# Sheet4.net
KiCad netlist of a schematic drawn in Altium Designer
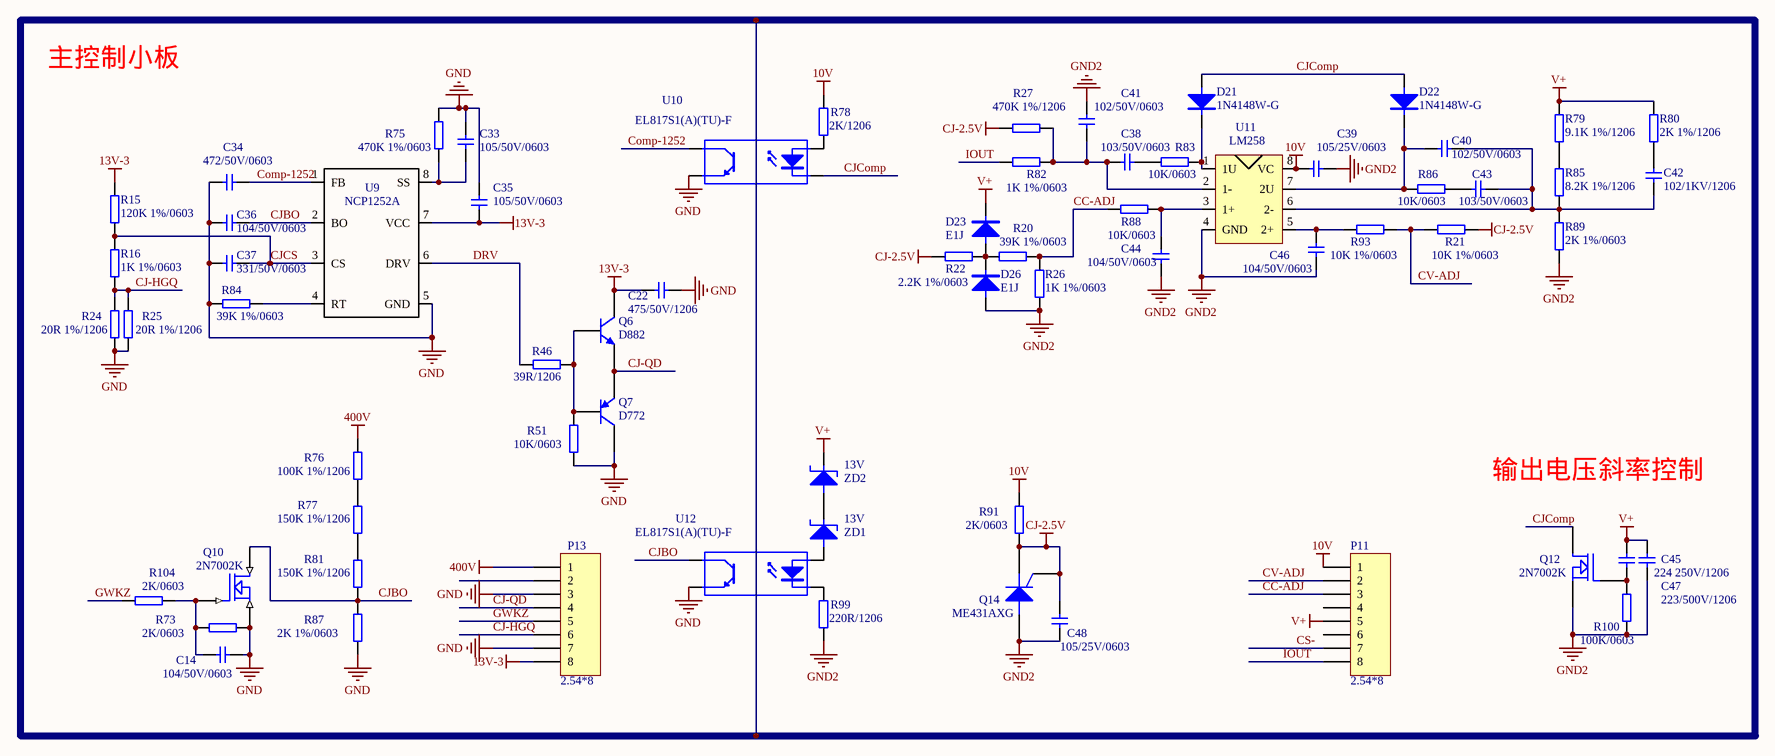
[diagram p0: Sheet4.SchDoc]

(export (version "E")
  (design (tool "Eeschema 10.0.6"))
  (components
    (comp (ref "C14")
      (value "104/50V/0603")
      (footprint "0603")
      (description "Capacitor")
      (libsource (lib "*") (part "CAP"))
    )
    (comp (ref "C22")
      (value "475/50V/1206")
      (footprint "1206")
      (description "Capacitor")
      (libsource (lib "*") (part "CAP"))
    )
    (comp (ref "C33")
      (value "105/50V/0603")
      (footprint "0603")
      (description "Capacitor")
      (libsource (lib "*") (part "CAP"))
    )
    (comp (ref "C34")
      (value "472/50V/0603")
      (footprint "0603")
      (description "Capacitor")
      (libsource (lib "*") (part "CAP"))
    )
    (comp (ref "C35")
      (value "105/50V/0603")
      (footprint "0603")
      (description "Capacitor")
      (libsource (lib "*") (part "CAP"))
    )
    (comp (ref "C36")
      (value "104/50V/0603")
      (footprint "0603")
      (description "Capacitor")
      (libsource (lib "*") (part "CAP"))
    )
    (comp (ref "C37")
      (value "331/50V/0603")
      (footprint "0603")
      (description "Capacitor")
      (libsource (lib "*") (part "CAP"))
    )
    (comp (ref "C38")
      (value "103/50V/0603")
      (footprint "0603")
      (description "Capacitor")
      (libsource (lib "*") (part "CAP"))
    )
    (comp (ref "C39")
      (value "105/25V/0603")
      (footprint "0603")
      (description "Capacitor")
      (libsource (lib "*") (part "CAP"))
    )
    (comp (ref "C40")
      (value "102/50V/0603")
      (footprint "0603")
      (description "Capacitor")
      (libsource (lib "*") (part "CAP"))
    )
    (comp (ref "C41")
      (value "102/50V/0603")
      (footprint "0603")
      (description "Capacitor")
      (libsource (lib "*") (part "CAP"))
    )
    (comp (ref "C42")
      (value "102/1KV/1206")
      (footprint "1206")
      (description "Capacitor")
      (libsource (lib "") (part "CAP_1"))
    )
    (comp (ref "C43")
      (value "103/50V/0603")
      (footprint "0603")
      (description "Capacitor")
      (libsource (lib "*") (part "CAP"))
    )
    (comp (ref "C44")
      (value "104/50V/0603")
      (footprint "0603")
      (description "Capacitor")
      (libsource (lib "*") (part "CAP"))
    )
    (comp (ref "C45")
      (value "224 250V/1206")
      (footprint "1206")
      (description "Capacitor")
      (libsource (lib "*") (part "CAP"))
    )
    (comp (ref "C46")
      (value "104/50V/0603")
      (footprint "0603")
      (description "Capacitor")
      (libsource (lib "*") (part "CAP"))
    )
    (comp (ref "C47")
      (value "223/500V/1206")
      (footprint "1206")
      (description "Capacitor")
      (libsource (lib "*") (part "CAP"))
    )
    (comp (ref "C48")
      (value "105/25V/0603")
      (footprint "0603")
      (description "Capacitor")
      (libsource (lib "*") (part "CAP"))
    )
    (comp (ref "D21")
      (value "1N4148W-G")
      (footprint "SOD-123")
      (description "Diode")
      (libsource (lib "sch123") (part "DIODE"))
    )
    (comp (ref "D22")
      (value "1N4148W-G")
      (footprint "SOD-123")
      (description "Diode")
      (libsource (lib "sch123") (part "DIODE"))
    )
    (comp (ref "D23")
      (value "E1J")
      (footprint "SOD-123")
      (description "Diode")
      (libsource (lib "sch123") (part "DIODE"))
    )
    (comp (ref "D26")
      (value "E1J")
      (footprint "SOD-123")
      (description "Diode")
      (libsource (lib "sch123") (part "DIODE"))
    )
    (comp (ref "P11")
      (value "2.54*8")
      (footprint "2.54*8")
      (description "Header, 8-Pin")
      (fields (field (name "PUBLISHER") "Altium Limited"))
      (libsource (lib "Miscellaneous Connectors") (part "Header 8"))
    )
    (comp (ref "P13")
      (value "2.54*8")
      (footprint "2.54*8")
      (description "Header, 8-Pin")
      (fields (field (name "PUBLISHER") "Altium Limited"))
      (libsource (lib "Miscellaneous Connectors") (part "Header 8"))
    )
    (comp (ref "Q6")
      (value "D882")
      (footprint "D882")
      (description "NPN General Purpose Amplifier")
      (fields (field (name "PUBLISHER") "Altium Limited"))
      (libsource (lib "Miscellaneous Devices") (part "2N3904"))
    )
    (comp (ref "Q7")
      (value "D772")
      (footprint "D772")
      (description "PNP General Purpose Amplifier")
      (fields (field (name "PUBLISHER") "Altium Limited"))
      (libsource (lib "Miscellaneous Devices") (part "2N3906"))
    )
    (comp (ref "Q10") (value "2N7002K") (footprint "SOT-23/MOS") (libsource (lib "sch123") (part "MOSFET N")))
    (comp (ref "Q12") (value "2N7002K") (footprint "SOT-23/MOS") (libsource (lib "sch123") (part "MOSFET N")))
    (comp (ref "Q14")
      (value "ME431AXG")
      (footprint "ME431AXG")
      (description "Silicon Controlled Rectifier")
      (fields (field (name "PUBLISHER") "Altium Limited"))
      (libsource (lib "Miscellaneous Devices") (part "SCR"))
    )
    (comp (ref "R15") (value "120K 1%/0603") (footprint "0603") (libsource (lib "*") (part "RES2")))
    (comp (ref "R16") (value "1K 1%/0603") (footprint "0603") (libsource (lib "*") (part "RES2")))
    (comp (ref "R20") (value "39K 1%/0603") (footprint "0603") (libsource (lib "sch123") (part "RES2")))
    (comp (ref "R21") (value "10K 1%/0603") (footprint "0603") (libsource (lib "sch123") (part "RES2")))
    (comp (ref "R22") (value "2.2K 1%/0603") (footprint "0603") (libsource (lib "sch123") (part "RES2")))
    (comp (ref "R24") (value "20R 1%/1206") (footprint "1206") (libsource (lib "*") (part "RES2")))
    (comp (ref "R25") (value "20R 1%/1206") (footprint "1206") (libsource (lib "*") (part "RES2")))
    (comp (ref "R26") (value "1K 1%/0603") (footprint "0603") (libsource (lib "sch123") (part "RES2")))
    (comp (ref "R27") (value "470K 1%/1206") (footprint "1206") (libsource (lib "sch123") (part "RES2")))
    (comp (ref "R46") (value "39R/1206") (footprint "1206") (libsource (lib "") (part "RES2_1")))
    (comp (ref "R51") (value "10K/0603") (footprint "0603") (libsource (lib "*") (part "RES2")))
    (comp (ref "R73") (value "2K/0603") (footprint "0603") (libsource (lib "sch123") (part "RES2")))
    (comp (ref "R75") (value "470K 1%/0603") (footprint "0603") (libsource (lib "sch123") (part "RES2")))
    (comp (ref "R76") (value "100K 1%/1206") (footprint "1206") (libsource (lib "*") (part "RES2")))
    (comp (ref "R77") (value "150K 1%/1206") (footprint "1206") (libsource (lib "*") (part "RES2")))
    (comp (ref "R78") (value "2K/1206") (footprint "1206") (libsource (lib "*") (part "RES2")))
    (comp (ref "R79") (value "9.1K 1%/1206") (footprint "1206") (libsource (lib "sch123") (part "RES2")))
    (comp (ref "R80") (value "2K 1%/1206") (footprint "1206") (libsource (lib "sch123") (part "RES2")))
    (comp (ref "R81") (value "150K 1%/1206") (footprint "1206") (libsource (lib "*") (part "RES2")))
    (comp (ref "R82") (value "1K 1%/0603") (footprint "0603") (libsource (lib "sch123") (part "RES2")))
    (comp (ref "R83") (value "10K/0603") (footprint "0603") (libsource (lib "sch123") (part "RES2")))
    (comp (ref "R84") (value "39K 1%/0603") (footprint "0603") (libsource (lib "sch123") (part "RES2")))
    (comp (ref "R85") (value "8.2K 1%/1206") (footprint "1206") (libsource (lib "sch123") (part "RES2")))
    (comp (ref "R86") (value "10K/0603") (footprint "0603") (libsource (lib "sch123") (part "RES2")))
    (comp (ref "R87") (value "2K 1%/0603") (footprint "0603") (libsource (lib "sch123") (part "RES2")))
    (comp (ref "R88") (value "10K/0603") (footprint "0603") (libsource (lib "sch123") (part "RES2")))
    (comp (ref "R89") (value "2K 1%/0603") (footprint "0603") (libsource (lib "sch123") (part "RES2")))
    (comp (ref "R91") (value "2K/0603") (footprint "0603") (libsource (lib "sch123") (part "RES2")))
    (comp (ref "R93") (value "10K 1%/0603") (footprint "0603") (libsource (lib "sch123") (part "RES2")))
    (comp (ref "R99") (value "220R/1206") (footprint "1206") (libsource (lib "*") (part "RES2")))
    (comp (ref "R100") (value "100K/0603") (footprint "0603") (libsource (lib "sch123") (part "RES2")))
    (comp (ref "R104") (value "2K/0603") (footprint "0603") (libsource (lib "sch123") (part "RES2")))
    (comp (ref "U9") (value "NCP1252A") (footprint "SOP8") (libsource (lib "Schlib1") (part "Component_1")))
    (comp (ref "U10")
      (value "EL817S1(A)(TU)-F")
      (footprint "EL817A")
      (description "4-Pin Phototransistor Optocoupler")
      (fields (field (name "PUBLISHER") "Altium Limited"))
      (libsource (lib "Miscellaneous Devices") (part "Optoisolator1"))
    )
    (comp (ref "U11") (value "LM258") (footprint "SOp8") (libsource (lib "Schlib1") (part "AP4310")))
    (comp (ref "U12")
      (value "EL817S1(A)(TU)-F")
      (footprint "EL817A")
      (description "4-Pin Phototransistor Optocoupler")
      (fields (field (name "PUBLISHER") "Altium Limited"))
      (libsource (lib "Miscellaneous Devices") (part "Optoisolator1"))
    )
    (comp (ref "ZD1")
      (value "13V")
      (footprint "SOD-123")
      (description "Diode Tunnel")
      (libsource (lib "sch123") (part "DIODE TUNNEL"))
    )
    (comp (ref "ZD2")
      (value "13V")
      (footprint "SOD-123")
      (description "Diode Tunnel")
      (libsource (lib "sch123") (part "DIODE TUNNEL"))
    )
  )
  (nets
    (net (code "1") (name "/CC-ADJ") (class "Default")
      (node (ref "P11") (pin "3") (pinfunction "3_3") (pintype "passive"))
      (node (ref "R20") (pin "2") (pinfunction "2_2") (pintype "passive"))
      (node (ref "R26") (pin "2") (pinfunction "2_2") (pintype "passive"))
      (node (ref "R88") (pin "1") (pinfunction "1_1") (pintype "passive"))
    )
    (net (code "2") (name "/CJ-HGQ") (class "Default")
      (node (ref "P13") (pin "6") (pinfunction "6_6") (pintype "passive"))
      (node (ref "R16") (pin "2") (pinfunction "2_2") (pintype "passive"))
      (node (ref "R24") (pin "1") (pinfunction "1_1") (pintype "passive"))
      (node (ref "R25") (pin "1") (pinfunction "1_1") (pintype "passive"))
    )
    (net (code "3") (name "/CJ-QD") (class "Default")
      (node (ref "P13") (pin "4") (pinfunction "4_4") (pintype "passive"))
      (node (ref "Q6") (pin "1") (pinfunction "E_1") (pintype "passive"))
      (node (ref "Q7") (pin "1") (pinfunction "E_1") (pintype "passive"))
    )
    (net (code "4") (name "/CJBO") (class "Default")
      (node (ref "C36") (pin "1") (pinfunction "1_1") (pintype "passive"))
      (node (ref "Q10") (pin "D") (pinfunction "D_D") (pintype "input"))
      (node (ref "R81") (pin "1") (pinfunction "1_1") (pintype "passive"))
      (node (ref "R87") (pin "1") (pinfunction "1_1") (pintype "passive"))
      (node (ref "U12") (pin "4") (pinfunction "C_4") (pintype "passive"))
      (node (ref "U9") (pin "2") (pinfunction "BO_2") (pintype "passive"))
    )
    (net (code "5") (name "/CJCS") (class "Default")
      (node (ref "C37") (pin "1") (pinfunction "1_1") (pintype "passive"))
      (node (ref "R15") (pin "2") (pinfunction "2_2") (pintype "passive"))
      (node (ref "R16") (pin "1") (pinfunction "1_1") (pintype "passive"))
      (node (ref "U9") (pin "3") (pinfunction "CS_3") (pintype "passive"))
    )
    (net (code "6") (name "/CJComp") (class "Default")
      (node (ref "D21") (pin "1") (pinfunction "A_1") (pintype "passive"))
      (node (ref "D22") (pin "1") (pinfunction "A_1") (pintype "passive"))
      (node (ref "Q12") (pin "D") (pinfunction "D_D") (pintype "input"))
      (node (ref "U10") (pin "2") (pinfunction "K_2") (pintype "passive"))
    )
    (net (code "7") (name "/CS-") (class "Default")
      (node (ref "P11") (pin "7") (pinfunction "7_7") (pintype "passive"))
    )
    (net (code "8") (name "/CV-ADJ") (class "Default")
      (node (ref "P11") (pin "2") (pinfunction "2_2") (pintype "passive"))
      (node (ref "R21") (pin "1") (pinfunction "1_1") (pintype "passive"))
      (node (ref "R93") (pin "2") (pinfunction "2_2") (pintype "passive"))
    )
    (net (code "9") (name "/Comp-1252") (class "Default")
      (node (ref "C34") (pin "1") (pinfunction "1_1") (pintype "passive"))
      (node (ref "U10") (pin "4") (pinfunction "C_4") (pintype "passive"))
      (node (ref "U9") (pin "1") (pinfunction "FB_1") (pintype "passive"))
    )
    (net (code "10") (name "/DRV") (class "Default")
      (node (ref "R46") (pin "2") (pinfunction "2_2") (pintype "passive"))
      (node (ref "U9") (pin "6") (pinfunction "DRV_6") (pintype "passive"))
    )
    (net (code "11") (name "/GWKZ") (class "Default")
      (node (ref "P13") (pin "5") (pinfunction "5_5") (pintype "passive"))
      (node (ref "R104") (pin "2") (pinfunction "2_2") (pintype "passive"))
    )
    (net (code "12") (name "/IOUT") (class "Default")
      (node (ref "P11") (pin "8") (pinfunction "8_8") (pintype "passive"))
      (node (ref "R82") (pin "2") (pinfunction "2_2") (pintype "passive"))
    )
    (net (code "13") (name "10V") (class "Default")
      (node (ref "C39") (pin "2") (pinfunction "2_2") (pintype "passive"))
      (node (ref "P11") (pin "1") (pinfunction "1_1") (pintype "passive"))
      (node (ref "R78") (pin "2") (pinfunction "2_2") (pintype "passive"))
      (node (ref "R91") (pin "2") (pinfunction "2_2") (pintype "passive"))
      (node (ref "U11") (pin "8") (pinfunction "VC_8") (pintype "passive"))
    )
    (net (code "14") (name "13V-3") (class "Default")
      (node (ref "C22") (pin "2") (pinfunction "2_2") (pintype "passive"))
      (node (ref "C35") (pin "1") (pinfunction "1_1") (pintype "passive"))
      (node (ref "P13") (pin "8") (pinfunction "8_8") (pintype "passive"))
      (node (ref "Q6") (pin "3") (pinfunction "C_3") (pintype "passive"))
      (node (ref "R15") (pin "1") (pinfunction "1_1") (pintype "passive"))
      (node (ref "U9") (pin "7") (pinfunction "VCC_7") (pintype "passive"))
    )
    (net (code "15") (name "400V") (class "Default")
      (node (ref "P13") (pin "1") (pinfunction "1_1") (pintype "passive"))
      (node (ref "R76") (pin "2") (pinfunction "2_2") (pintype "passive"))
    )
    (net (code "16") (name "CJ-2.5V") (class "Default")
      (node (ref "C48") (pin "2") (pinfunction "2_2") (pintype "passive"))
      (node (ref "Q14") (pin "2") (pinfunction "G_2") (pintype "passive"))
      (node (ref "Q14") (pin "3") (pinfunction "K_3") (pintype "passive"))
      (node (ref "R21") (pin "2") (pinfunction "2_2") (pintype "passive"))
      (node (ref "R22") (pin "1") (pinfunction "1_1") (pintype "passive"))
      (node (ref "R27") (pin "2") (pinfunction "2_2") (pintype "passive"))
      (node (ref "R91") (pin "1") (pinfunction "1_1") (pintype "passive"))
    )
    (net (code "17") (name "GND") (class "Default")
      (node (ref "C14") (pin "1") (pinfunction "1_1") (pintype "passive"))
      (node (ref "C22") (pin "1") (pinfunction "1_1") (pintype "passive"))
      (node (ref "C33") (pin "2") (pinfunction "2_2") (pintype "passive"))
      (node (ref "C34") (pin "2") (pinfunction "2_2") (pintype "passive"))
      (node (ref "C35") (pin "2") (pinfunction "2_2") (pintype "passive"))
      (node (ref "C36") (pin "2") (pinfunction "2_2") (pintype "passive"))
      (node (ref "C37") (pin "2") (pinfunction "2_2") (pintype "passive"))
      (node (ref "P13") (pin "3") (pinfunction "3_3") (pintype "passive"))
      (node (ref "P13") (pin "7") (pinfunction "7_7") (pintype "passive"))
      (node (ref "Q10") (pin "S") (pinfunction "S_S") (pintype "input"))
      (node (ref "Q7") (pin "3") (pinfunction "C_3") (pintype "passive"))
      (node (ref "R24") (pin "2") (pinfunction "2_2") (pintype "passive"))
      (node (ref "R25") (pin "2") (pinfunction "2_2") (pintype "passive"))
      (node (ref "R51") (pin "1") (pinfunction "1_1") (pintype "passive"))
      (node (ref "R73") (pin "1") (pinfunction "1_1") (pintype "passive"))
      (node (ref "R75") (pin "2") (pinfunction "2_2") (pintype "passive"))
      (node (ref "R84") (pin "1") (pinfunction "1_1") (pintype "passive"))
      (node (ref "R87") (pin "2") (pinfunction "2_2") (pintype "passive"))
      (node (ref "U10") (pin "3") (pinfunction "E_3") (pintype "passive"))
      (node (ref "U12") (pin "3") (pinfunction "E_3") (pintype "passive"))
      (node (ref "U9") (pin "5") (pinfunction "GND_5") (pintype "passive"))
    )
    (net (code "18") (name "GND2") (class "Default")
      (node (ref "C39") (pin "1") (pinfunction "1_1") (pintype "passive"))
      (node (ref "C41") (pin "2") (pinfunction "2_2") (pintype "passive"))
      (node (ref "C44") (pin "1") (pinfunction "1_1") (pintype "passive"))
      (node (ref "C45") (pin "2") (pinfunction "2_2") (pintype "passive"))
      (node (ref "C46") (pin "2") (pinfunction "2_2") (pintype "passive"))
      (node (ref "C48") (pin "1") (pinfunction "1_1") (pintype "passive"))
      (node (ref "D26") (pin "1") (pinfunction "A_1") (pintype "passive"))
      (node (ref "Q12") (pin "S") (pinfunction "S_S") (pintype "input"))
      (node (ref "Q14") (pin "1") (pinfunction "A_1") (pintype "passive"))
      (node (ref "R100") (pin "1") (pinfunction "1_1") (pintype "passive"))
      (node (ref "R26") (pin "1") (pinfunction "1_1") (pintype "passive"))
      (node (ref "R89") (pin "1") (pinfunction "1_1") (pintype "passive"))
      (node (ref "R99") (pin "1") (pinfunction "1_1") (pintype "passive"))
      (node (ref "U11") (pin "4") (pinfunction "GND_4") (pintype "passive"))
    )
    (net (code "19") (name "Net-(C14-Pad2)") (class "Default")
      (node (ref "C14") (pin "2") (pinfunction "2_2") (pintype "passive"))
      (node (ref "Q10") (pin "G") (pinfunction "G_G") (pintype "input"))
      (node (ref "R104") (pin "1") (pinfunction "1_1") (pintype "passive"))
      (node (ref "R73") (pin "2") (pinfunction "2_2") (pintype "passive"))
    )
    (net (code "20") (name "Net-(C38-Pad1)") (class "Default")
      (node (ref "C38") (pin "1") (pinfunction "1_1") (pintype "passive"))
      (node (ref "R83") (pin "1") (pinfunction "1_1") (pintype "passive"))
    )
    (net (code "21") (name "Net-(C42-Pad2)") (class "Default")
      (node (ref "C42") (pin "2") (pinfunction "2_2") (pintype "passive"))
      (node (ref "R80") (pin "1") (pinfunction "1_1") (pintype "passive"))
    )
    (net (code "22") (name "Net-(C43-Pad2)") (class "Default")
      (node (ref "C43") (pin "2") (pinfunction "2_2") (pintype "passive"))
      (node (ref "R86") (pin "2") (pinfunction "2_2") (pintype "passive"))
    )
    (net (code "23") (name "Net-(C47-Pad2)") (class "Default")
      (node (ref "C47") (pin "2") (pinfunction "2_2") (pintype "passive"))
      (node (ref "Q12") (pin "G") (pinfunction "G_G") (pintype "input"))
      (node (ref "R100") (pin "2") (pinfunction "2_2") (pintype "passive"))
    )
    (net (code "24") (name "Net-(D21-K)") (class "Default")
      (node (ref "D21") (pin "2") (pinfunction "K_2") (pintype "passive"))
      (node (ref "R83") (pin "2") (pinfunction "2_2") (pintype "passive"))
      (node (ref "U11") (pin "1") (pinfunction "1U_1") (pintype "passive"))
    )
    (net (code "25") (name "Net-(D22-K)") (class "Default")
      (node (ref "C40") (pin "2") (pinfunction "2_2") (pintype "passive"))
      (node (ref "D22") (pin "2") (pinfunction "K_2") (pintype "passive"))
      (node (ref "R86") (pin "1") (pinfunction "1_1") (pintype "passive"))
      (node (ref "U11") (pin "7") (pinfunction "2U_7") (pintype "passive"))
    )
    (net (code "26") (name "Net-(D23-A)") (class "Default")
      (node (ref "D23") (pin "1") (pinfunction "A_1") (pintype "passive"))
      (node (ref "D26") (pin "2") (pinfunction "K_2") (pintype "passive"))
      (node (ref "R20") (pin "1") (pinfunction "1_1") (pintype "passive"))
      (node (ref "R22") (pin "2") (pinfunction "2_2") (pintype "passive"))
    )
    (net (code "27") (name "Net-(Q6-B)") (class "Default")
      (node (ref "Q6") (pin "2") (pinfunction "B_2") (pintype "passive"))
      (node (ref "Q7") (pin "2") (pinfunction "B_2") (pintype "passive"))
      (node (ref "R46") (pin "1") (pinfunction "1_1") (pintype "passive"))
      (node (ref "R51") (pin "2") (pinfunction "2_2") (pintype "passive"))
    )
    (net (code "28") (name "Net-(R76-Pad1)") (class "Default")
      (node (ref "R76") (pin "1") (pinfunction "1_1") (pintype "passive"))
      (node (ref "R77") (pin "2") (pinfunction "2_2") (pintype "passive"))
    )
    (net (code "29") (name "Net-(R77-Pad1)") (class "Default")
      (node (ref "R77") (pin "1") (pinfunction "1_1") (pintype "passive"))
      (node (ref "R81") (pin "2") (pinfunction "2_2") (pintype "passive"))
    )
    (net (code "30") (name "Net-(R79-Pad1)") (class "Default")
      (node (ref "R79") (pin "1") (pinfunction "1_1") (pintype "passive"))
      (node (ref "R85") (pin "2") (pinfunction "2_2") (pintype "passive"))
    )
    (net (code "31") (name "Net-(U9-RT)") (class "Default")
      (node (ref "R84") (pin "2") (pinfunction "2_2") (pintype "passive"))
      (node (ref "U9") (pin "4") (pinfunction "RT_4") (pintype "passive"))
    )
    (net (code "32") (name "Net-(U9-SS)") (class "Default")
      (node (ref "C33") (pin "1") (pinfunction "1_1") (pintype "passive"))
      (node (ref "R75") (pin "1") (pinfunction "1_1") (pintype "passive"))
      (node (ref "U9") (pin "8") (pinfunction "SS_8") (pintype "passive"))
    )
    (net (code "33") (name "Net-(U10-A)") (class "Default")
      (node (ref "R78") (pin "1") (pinfunction "1_1") (pintype "passive"))
      (node (ref "U10") (pin "1") (pinfunction "A_1") (pintype "passive"))
    )
    (net (code "34") (name "Net-(U11-1+)") (class "Default")
      (node (ref "C44") (pin "2") (pinfunction "2_2") (pintype "passive"))
      (node (ref "R88") (pin "2") (pinfunction "2_2") (pintype "passive"))
      (node (ref "U11") (pin "3") (pinfunction "1+_3") (pintype "passive"))
    )
    (net (code "35") (name "Net-(U11-1-)") (class "Default")
      (node (ref "C38") (pin "2") (pinfunction "2_2") (pintype "passive"))
      (node (ref "C41") (pin "1") (pinfunction "1_1") (pintype "passive"))
      (node (ref "R27") (pin "1") (pinfunction "1_1") (pintype "passive"))
      (node (ref "R82") (pin "1") (pinfunction "1_1") (pintype "passive"))
      (node (ref "U11") (pin "2") (pinfunction "1-_2") (pintype "passive"))
    )
    (net (code "36") (name "Net-(U11-2+)") (class "Default")
      (node (ref "C46") (pin "1") (pinfunction "1_1") (pintype "passive"))
      (node (ref "R93") (pin "1") (pinfunction "1_1") (pintype "passive"))
      (node (ref "U11") (pin "5") (pinfunction "2+_5") (pintype "passive"))
    )
    (net (code "37") (name "Net-(U11-2-)") (class "Default")
      (node (ref "C40") (pin "1") (pinfunction "1_1") (pintype "passive"))
      (node (ref "C42") (pin "1") (pinfunction "1_1") (pintype "passive"))
      (node (ref "C43") (pin "1") (pinfunction "1_1") (pintype "passive"))
      (node (ref "R85") (pin "1") (pinfunction "1_1") (pintype "passive"))
      (node (ref "R89") (pin "2") (pinfunction "2_2") (pintype "passive"))
      (node (ref "U11") (pin "6") (pinfunction "2-_6") (pintype "passive"))
    )
    (net (code "38") (name "Net-(U12-A)") (class "Default")
      (node (ref "U12") (pin "1") (pinfunction "A_1") (pintype "passive"))
      (node (ref "ZD1") (pin "1") (pinfunction "A_1") (pintype "passive"))
    )
    (net (code "39") (name "Net-(U12-K)") (class "Default")
      (node (ref "R99") (pin "2") (pinfunction "2_2") (pintype "passive"))
      (node (ref "U12") (pin "2") (pinfunction "K_2") (pintype "passive"))
    )
    (net (code "40") (name "Net-(ZD1-K)") (class "Default")
      (node (ref "ZD1") (pin "2") (pinfunction "K_2") (pintype "passive"))
      (node (ref "ZD2") (pin "1") (pinfunction "A_1") (pintype "passive"))
    )
    (net (code "41") (name "V+") (class "Default")
      (node (ref "C45") (pin "1") (pinfunction "1_1") (pintype "passive"))
      (node (ref "C47") (pin "1") (pinfunction "1_1") (pintype "passive"))
      (node (ref "D23") (pin "2") (pinfunction "K_2") (pintype "passive"))
      (node (ref "P11") (pin "5") (pinfunction "5_5") (pintype "passive"))
      (node (ref "R79") (pin "2") (pinfunction "2_2") (pintype "passive"))
      (node (ref "R80") (pin "2") (pinfunction "2_2") (pintype "passive"))
      (node (ref "ZD2") (pin "2") (pinfunction "K_2") (pintype "passive"))
    )
    (net (code "42") (name "unconnected-(P11-Pad4)") (class "Default")
      (node (ref "P11") (pin "4") (pinfunction "4_4") (pintype "passive"))
    )
    (net (code "43") (name "unconnected-(P11-Pad6)") (class "Default")
      (node (ref "P11") (pin "6") (pinfunction "6_6") (pintype "passive"))
    )
    (net (code "44") (name "unconnected-(P13-Pad2)") (class "Default")
      (node (ref "P13") (pin "2") (pinfunction "2_2") (pintype "passive"))
    )
  )
)
